# Sensor_LM35_Package.net
KiCad netlist of a schematic drawn in Altium Designer
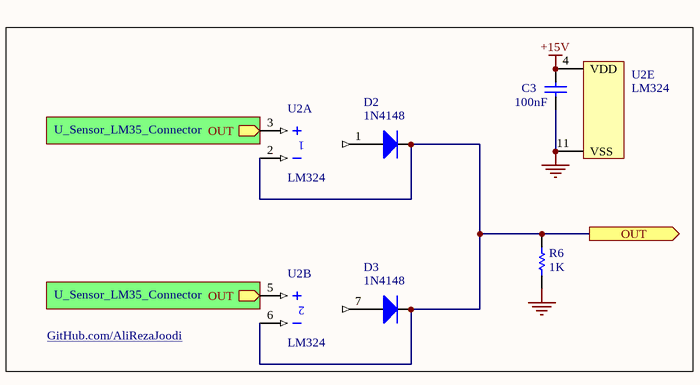
[diagram p0: Sensor_LM35_Package.SchDoc]

(export (version "E")
  (design (tool "Eeschema 10.0.6"))
  (components
    (comp (ref "C3")
      (value "100nF")
      (footprint "CAPNTO2.54-3.05x1.78A")
      (description "Capacitor")
      (fields (field (name "MANUFACTURER") "Generic Components") (field (name "PUBLISHER") "Altium Limited"))
      (libsource (lib "Miscellaneous Devices") (part "Cap"))
    )
    (comp (ref "D2")
      (value "1N4148")
      (footprint "DIODE0.4_Glass")
      (description "Default Diode")
      (fields (field (name "MANUFACTURER") "Generic Components") (field (name "PUBLISHER") "Altium Limited"))
      (libsource (lib "Miscellaneous Devices") (part "Diode"))
    )
    (comp (ref "D3")
      (value "1N4148")
      (footprint "DIODE0.4_Glass")
      (description "Default Diode")
      (fields (field (name "MANUFACTURER") "Generic Components") (field (name "PUBLISHER") "Altium Limited"))
      (libsource (lib "Miscellaneous Devices") (part "Diode"))
    )
    (comp (ref "R6")
      (value "1K")
      (footprint "AXIAL-0.4")
      (description "Resistor")
      (fields (field (name "PUBLISHER") "Altium Limited"))
      (libsource (lib "Miscellaneous Devices") (part "Res1"))
    )
    (comp (ref "U2")
      (value "LM324")
      (footprint "646-06")
      (description "Quad Low-Power Operational Amplifier")
      (fields (field (name "PUBLISHER") "Altium Limited"))
      (libsource (lib "my Libraries") (part "LM324"))
    )
  )
  (nets
    (net (code "1") (name "+15V") (class "Default")
      (node (ref "C3") (pin "2") (pinfunction "2_2") (pintype "passive"))
      (node (ref "U2") (pin "4") (pinfunction "VDD_4") (pintype "passive"))
    )
    (net (code "2") (name "/OUT") (class "Default")
      (node (ref "D2") (pin "2") (pinfunction "K_2") (pintype "passive"))
      (node (ref "D3") (pin "2") (pinfunction "K_2") (pintype "passive"))
      (node (ref "R6") (pin "1") (pinfunction "1_1") (pintype "passive"))
      (node (ref "U2") (pin "2") (pinfunction "IN-_2") (pintype "input"))
      (node (ref "U2") (pin "6") (pinfunction "IN-_6") (pintype "input"))
    )
    (net (code "3") (name "/OUT_1") (class "Default")
      (node (ref "U2") (pin "5") (pinfunction "IN+_5") (pintype "input"))
    )
    (net (code "4") (name "/OUT_2") (class "Default")
      (node (ref "U2") (pin "3") (pinfunction "IN+_3") (pintype "input"))
    )
    (net (code "5") (name "GND") (class "Default")
      (node (ref "C3") (pin "1") (pinfunction "1_1") (pintype "passive"))
      (node (ref "R6") (pin "2") (pinfunction "2_2") (pintype "passive"))
      (node (ref "U2") (pin "11") (pinfunction "VSS_11") (pintype "power_in"))
    )
    (net (code "6") (name "Net-(D2-A)") (class "Default")
      (node (ref "D2") (pin "1") (pinfunction "A_1") (pintype "passive"))
      (node (ref "U2") (pin "1") (pinfunction "OUT_1") (pintype "output"))
    )
    (net (code "7") (name "Net-(D3-A)") (class "Default")
      (node (ref "D3") (pin "1") (pinfunction "A_1") (pintype "passive"))
      (node (ref "U2") (pin "7") (pinfunction "OUT_7") (pintype "output"))
    )
  )
)
